# hybrid_esc.net
KiCad netlist of a schematic drawn in EAGLE
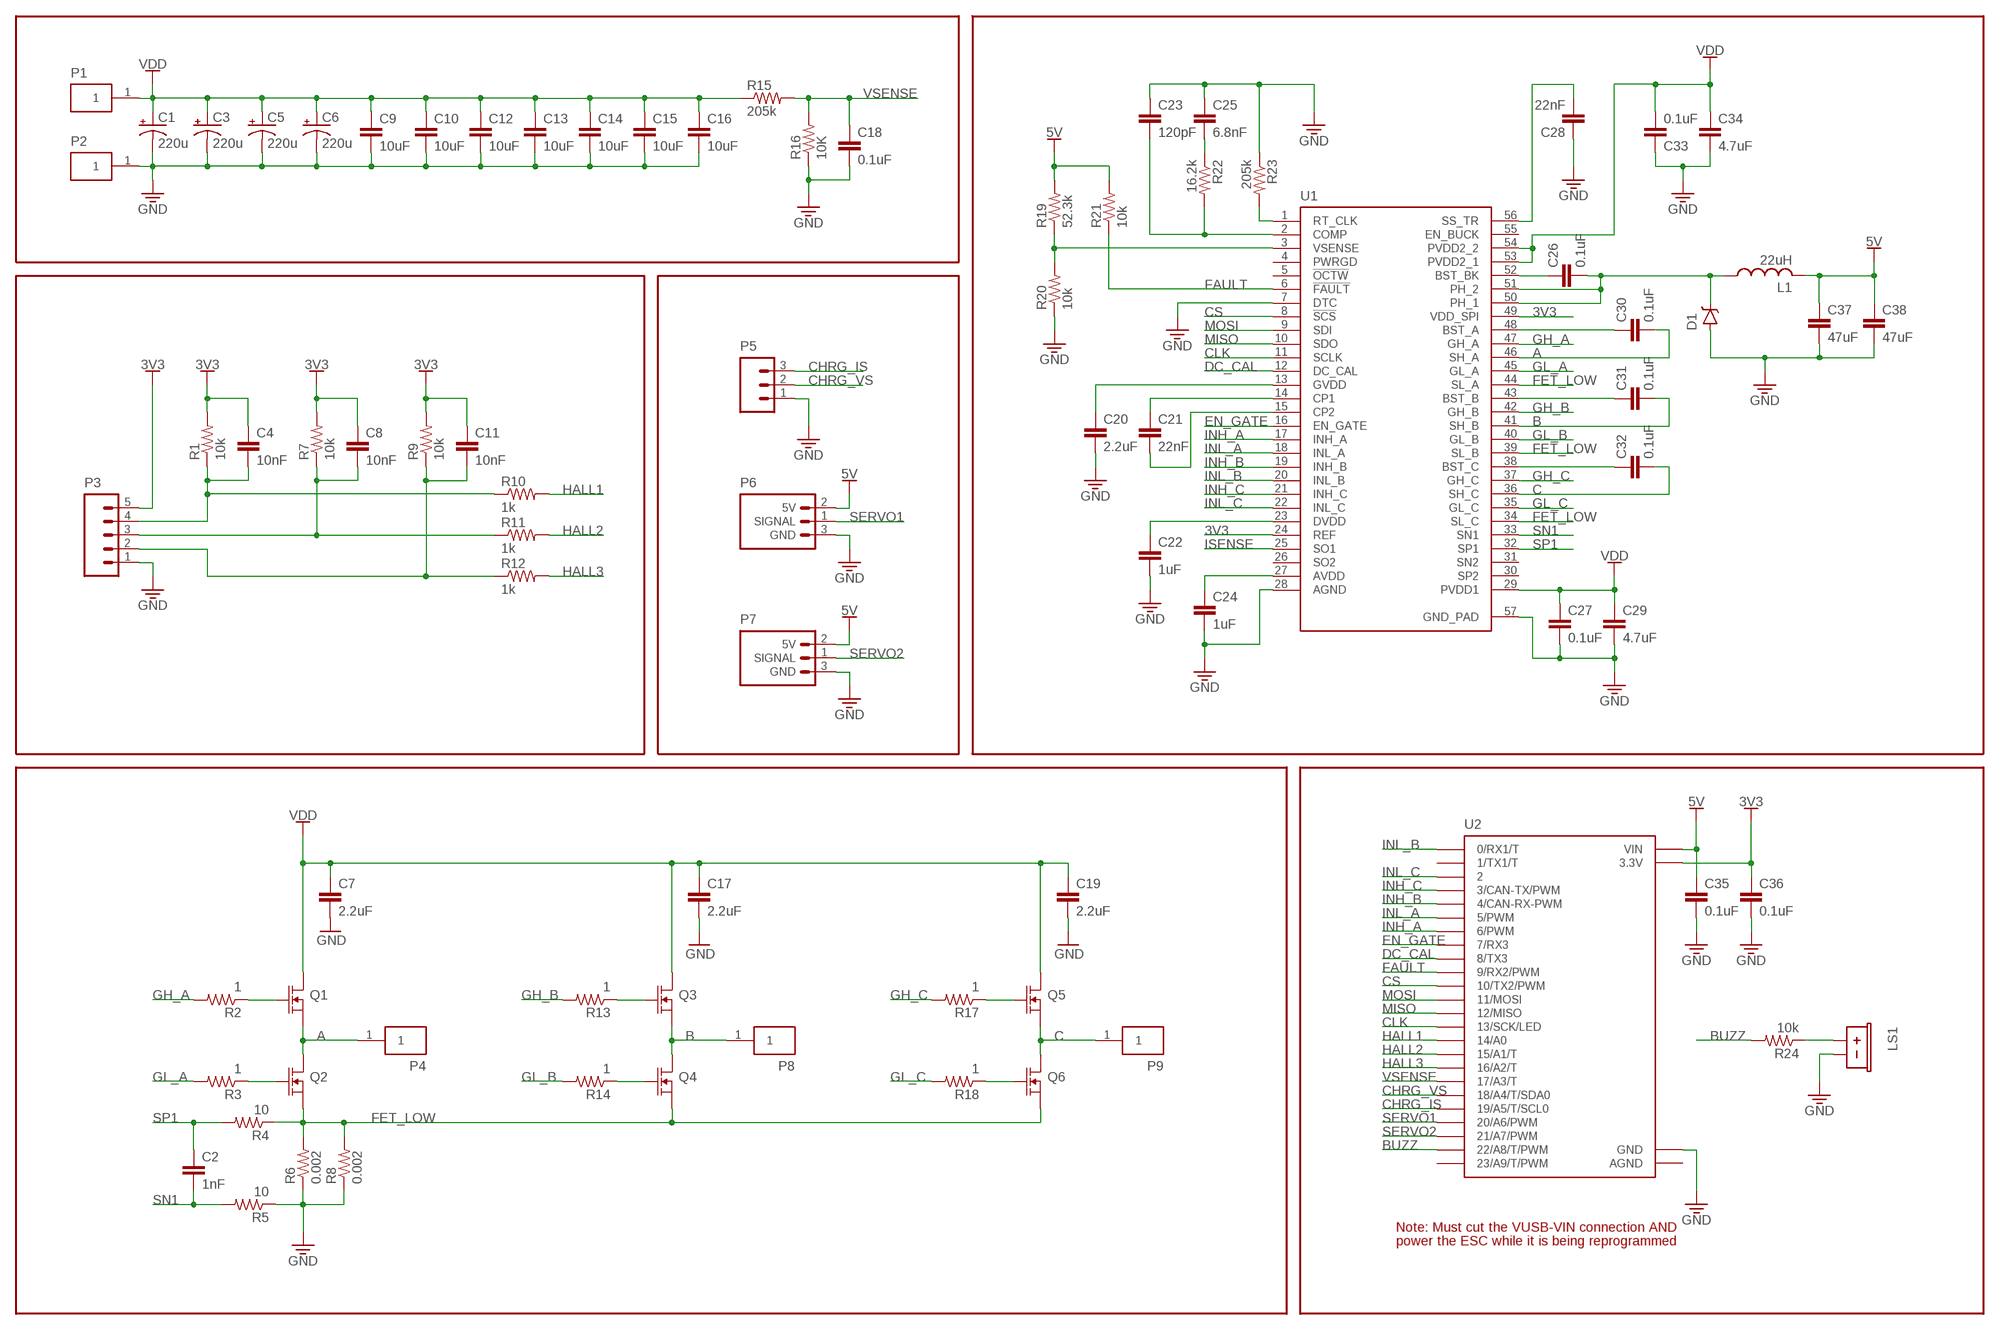
[diagram p0: schematic, sheet 1]

(export (version "E")
  (design (tool "Eeschema 10.0.6"))
  (components
    (comp (ref "C1")
      (value "220u")
      (footprint "eagle-import:CPOL_10_5")
      (libsource (lib "eagle-import") (part "CPOL_10_5"))
    )
    (comp (ref "C2")
      (value "1nF")
      (footprint "eagle-import:C0603")
      (libsource (lib "eagle-import") (part "C0603"))
    )
    (comp (ref "C3")
      (value "220u")
      (footprint "eagle-import:CPOL_10_5")
      (libsource (lib "eagle-import") (part "CPOL_10_5"))
    )
    (comp (ref "C4")
      (value "10nF")
      (footprint "eagle-import:C0603")
      (libsource (lib "eagle-import") (part "C0603"))
    )
    (comp (ref "C5")
      (value "220u")
      (footprint "eagle-import:CPOL_10_5")
      (libsource (lib "eagle-import") (part "CPOL_10_5"))
    )
    (comp (ref "C6")
      (value "220u")
      (footprint "eagle-import:CPOL_10_5")
      (libsource (lib "eagle-import") (part "CPOL_10_5"))
    )
    (comp (ref "C7")
      (value "2.2uF")
      (footprint "eagle-import:C1206")
      (libsource (lib "eagle-import") (part "C1206"))
    )
    (comp (ref "C8")
      (value "10nF")
      (footprint "eagle-import:C0603")
      (libsource (lib "eagle-import") (part "C0603"))
    )
    (comp (ref "C9")
      (value "10uF")
      (footprint "eagle-import:C1206")
      (libsource (lib "eagle-import") (part "C1206"))
    )
    (comp (ref "C10")
      (value "10uF")
      (footprint "eagle-import:C1206")
      (libsource (lib "eagle-import") (part "C1206"))
    )
    (comp (ref "C11")
      (value "10nF")
      (footprint "eagle-import:C0603")
      (libsource (lib "eagle-import") (part "C0603"))
    )
    (comp (ref "C12")
      (value "10uF")
      (footprint "eagle-import:C1206")
      (libsource (lib "eagle-import") (part "C1206"))
    )
    (comp (ref "C13")
      (value "10uF")
      (footprint "eagle-import:C1206")
      (libsource (lib "eagle-import") (part "C1206"))
    )
    (comp (ref "C14")
      (value "10uF")
      (footprint "eagle-import:C1206")
      (libsource (lib "eagle-import") (part "C1206"))
    )
    (comp (ref "C15")
      (value "10uF")
      (footprint "eagle-import:C1206")
      (libsource (lib "eagle-import") (part "C1206"))
    )
    (comp (ref "C16")
      (value "10uF")
      (footprint "eagle-import:C1206")
      (libsource (lib "eagle-import") (part "C1206"))
    )
    (comp (ref "C17")
      (value "2.2uF")
      (footprint "eagle-import:C1206")
      (libsource (lib "eagle-import") (part "C1206"))
    )
    (comp (ref "C18")
      (value "0.1uF")
      (footprint "eagle-import:C0603")
      (libsource (lib "eagle-import") (part "C0603"))
    )
    (comp (ref "C19")
      (value "2.2uF")
      (footprint "eagle-import:C1206")
      (libsource (lib "eagle-import") (part "C1206"))
    )
    (comp (ref "C20")
      (value "2.2uF")
      (footprint "eagle-import:C0603")
      (libsource (lib "eagle-import") (part "C0603"))
    )
    (comp (ref "C21")
      (value "22nF")
      (footprint "eagle-import:C0603")
      (libsource (lib "eagle-import") (part "C0603"))
    )
    (comp (ref "C22")
      (value "1uF")
      (footprint "eagle-import:C0603")
      (libsource (lib "eagle-import") (part "C0603"))
    )
    (comp (ref "C23")
      (value "120pF")
      (footprint "eagle-import:C0603")
      (libsource (lib "eagle-import") (part "C0603"))
    )
    (comp (ref "C24")
      (value "1uF")
      (footprint "eagle-import:C0603")
      (libsource (lib "eagle-import") (part "C0603"))
    )
    (comp (ref "C25")
      (value "6.8nF")
      (footprint "eagle-import:C0603")
      (libsource (lib "eagle-import") (part "C0603"))
    )
    (comp (ref "C26")
      (value "0.1uF")
      (footprint "eagle-import:C0603")
      (libsource (lib "eagle-import") (part "C0603"))
    )
    (comp (ref "C27")
      (value "0.1uF")
      (footprint "eagle-import:C0603")
      (libsource (lib "eagle-import") (part "C0603"))
    )
    (comp (ref "C28")
      (value "22nF")
      (footprint "eagle-import:C0603")
      (libsource (lib "eagle-import") (part "C0603"))
    )
    (comp (ref "C29")
      (value "4.7uF")
      (footprint "eagle-import:C1206")
      (libsource (lib "eagle-import") (part "C1206"))
    )
    (comp (ref "C30")
      (value "0.1uF")
      (footprint "eagle-import:C0603")
      (libsource (lib "eagle-import") (part "C0603"))
    )
    (comp (ref "C31")
      (value "0.1uF")
      (footprint "eagle-import:C0603")
      (libsource (lib "eagle-import") (part "C0603"))
    )
    (comp (ref "C32")
      (value "0.1uF")
      (footprint "eagle-import:C0603")
      (libsource (lib "eagle-import") (part "C0603"))
    )
    (comp (ref "C33")
      (value "0.1uF")
      (footprint "eagle-import:C0603")
      (libsource (lib "eagle-import") (part "C0603"))
    )
    (comp (ref "C34")
      (value "4.7uF")
      (footprint "eagle-import:C1206")
      (libsource (lib "eagle-import") (part "C1206"))
    )
    (comp (ref "C35")
      (value "0.1uF")
      (footprint "eagle-import:C0603")
      (libsource (lib "eagle-import") (part "C0603"))
    )
    (comp (ref "C36")
      (value "0.1uF")
      (footprint "eagle-import:C0603")
      (libsource (lib "eagle-import") (part "C0603"))
    )
    (comp (ref "C37")
      (value "47uF")
      (footprint "eagle-import:C1206")
      (libsource (lib "eagle-import") (part "C1206"))
    )
    (comp (ref "C38")
      (value "47uF")
      (footprint "eagle-import:C1206")
      (libsource (lib "eagle-import") (part "C1206"))
    )
    (comp (ref "D1")
      (value "D_SOD123W")
      (footprint "eagle-import:SOD123W")
      (libsource (lib "eagle-import") (part "D_SOD123W"))
    )
    (comp (ref "L1")
      (value "22uH")
      (footprint "eagle-import:SDR0805")
      (libsource (lib "eagle-import") (part "L_SDR0805"))
    )
    (comp (ref "LS1")
      (value "BUZZER_12MM")
      (footprint "eagle-import:BUZZER_12MM")
      (libsource (lib "eagle-import") (part "BUZZER_12MM"))
    )
    (comp (ref "P1")
      (value "POWER_PAD")
      (footprint "eagle-import:POWER_PAD")
      (libsource (lib "eagle-import") (part "POWER_PAD"))
    )
    (comp (ref "P2")
      (value "POWER_PAD")
      (footprint "eagle-import:POWER_PAD")
      (libsource (lib "eagle-import") (part "POWER_PAD"))
    )
    (comp (ref "P3")
      (value "JST-XH5")
      (footprint "eagle-import:JST-XH5")
      (libsource (lib "eagle-import") (part "JST-XH5"))
    )
    (comp (ref "P4")
      (value "POWER_PAD")
      (footprint "eagle-import:POWER_PAD")
      (libsource (lib "eagle-import") (part "POWER_PAD"))
    )
    (comp (ref "P5")
      (value "CONN_03")
      (footprint "eagle-import:CONN_03")
      (libsource (lib "eagle-import") (part "CONN_03"))
    )
    (comp (ref "P6")
      (value "SERVO")
      (footprint "eagle-import:SERVO")
      (libsource (lib "eagle-import") (part "SERVO"))
    )
    (comp (ref "P7")
      (value "SERVO")
      (footprint "eagle-import:SERVO")
      (libsource (lib "eagle-import") (part "SERVO"))
    )
    (comp (ref "P8")
      (value "POWER_PAD")
      (footprint "eagle-import:POWER_PAD")
      (libsource (lib "eagle-import") (part "POWER_PAD"))
    )
    (comp (ref "P9")
      (value "POWER_PAD")
      (footprint "eagle-import:POWER_PAD")
      (libsource (lib "eagle-import") (part "POWER_PAD"))
    )
    (comp (ref "Q1")
      (value "NFET_D2PAK-7")
      (footprint "eagle-import:D2PAK-7")
      (libsource (lib "eagle-import") (part "NFET_D2PAK-7"))
    )
    (comp (ref "Q2")
      (value "NFET_D2PAK-7")
      (footprint "eagle-import:D2PAK-7")
      (libsource (lib "eagle-import") (part "NFET_D2PAK-7"))
    )
    (comp (ref "Q3")
      (value "NFET_D2PAK-7")
      (footprint "eagle-import:D2PAK-7")
      (libsource (lib "eagle-import") (part "NFET_D2PAK-7"))
    )
    (comp (ref "Q4")
      (value "NFET_D2PAK-7")
      (footprint "eagle-import:D2PAK-7")
      (libsource (lib "eagle-import") (part "NFET_D2PAK-7"))
    )
    (comp (ref "Q5")
      (value "NFET_D2PAK-7")
      (footprint "eagle-import:D2PAK-7")
      (libsource (lib "eagle-import") (part "NFET_D2PAK-7"))
    )
    (comp (ref "Q6")
      (value "NFET_D2PAK-7")
      (footprint "eagle-import:D2PAK-7")
      (libsource (lib "eagle-import") (part "NFET_D2PAK-7"))
    )
    (comp (ref "R1")
      (value "10k")
      (footprint "eagle-import:R0603")
      (libsource (lib "eagle-import") (part "R0603"))
    )
    (comp (ref "R2")
      (value "1")
      (footprint "eagle-import:R0603")
      (libsource (lib "eagle-import") (part "R0603"))
    )
    (comp (ref "R3")
      (value "1")
      (footprint "eagle-import:R0603")
      (libsource (lib "eagle-import") (part "R0603"))
    )
    (comp (ref "R4")
      (value "10")
      (footprint "eagle-import:R0603")
      (libsource (lib "eagle-import") (part "R0603"))
    )
    (comp (ref "R5")
      (value "10")
      (footprint "eagle-import:R0603")
      (libsource (lib "eagle-import") (part "R0603"))
    )
    (comp (ref "R6")
      (value "0.002")
      (footprint "eagle-import:R2512")
      (libsource (lib "eagle-import") (part "R2512"))
    )
    (comp (ref "R7")
      (value "10k")
      (footprint "eagle-import:R0603")
      (libsource (lib "eagle-import") (part "R0603"))
    )
    (comp (ref "R8")
      (value "0.002")
      (footprint "eagle-import:R2512")
      (libsource (lib "eagle-import") (part "R2512"))
    )
    (comp (ref "R9")
      (value "10k")
      (footprint "eagle-import:R0603")
      (libsource (lib "eagle-import") (part "R0603"))
    )
    (comp (ref "R10")
      (value "1k")
      (footprint "eagle-import:R0603")
      (libsource (lib "eagle-import") (part "R0603"))
    )
    (comp (ref "R11")
      (value "1k")
      (footprint "eagle-import:R0603")
      (libsource (lib "eagle-import") (part "R0603"))
    )
    (comp (ref "R12")
      (value "1k")
      (footprint "eagle-import:R0603")
      (libsource (lib "eagle-import") (part "R0603"))
    )
    (comp (ref "R13")
      (value "1")
      (footprint "eagle-import:R0603")
      (libsource (lib "eagle-import") (part "R0603"))
    )
    (comp (ref "R14")
      (value "1")
      (footprint "eagle-import:R0603")
      (libsource (lib "eagle-import") (part "R0603"))
    )
    (comp (ref "R15")
      (value "205k")
      (footprint "eagle-import:R0603")
      (libsource (lib "eagle-import") (part "R0603"))
    )
    (comp (ref "R16")
      (value "10K")
      (footprint "eagle-import:R0603")
      (libsource (lib "eagle-import") (part "R0603"))
    )
    (comp (ref "R17")
      (value "1")
      (footprint "eagle-import:R0603")
      (libsource (lib "eagle-import") (part "R0603"))
    )
    (comp (ref "R18")
      (value "1")
      (footprint "eagle-import:R0603")
      (libsource (lib "eagle-import") (part "R0603"))
    )
    (comp (ref "R19")
      (value "52.3k")
      (footprint "eagle-import:R0603")
      (libsource (lib "eagle-import") (part "R0603"))
    )
    (comp (ref "R20")
      (value "10k")
      (footprint "eagle-import:R0603")
      (libsource (lib "eagle-import") (part "R0603"))
    )
    (comp (ref "R21")
      (value "10k")
      (footprint "eagle-import:R0603")
      (libsource (lib "eagle-import") (part "R0603"))
    )
    (comp (ref "R22")
      (value "16.2k")
      (footprint "eagle-import:R0603")
      (libsource (lib "eagle-import") (part "R0603"))
    )
    (comp (ref "R23")
      (value "205k")
      (footprint "eagle-import:R0603")
      (libsource (lib "eagle-import") (part "R0603"))
    )
    (comp (ref "R24")
      (value "10k")
      (footprint "eagle-import:R0603")
      (libsource (lib "eagle-import") (part "R0603"))
    )
    (comp (ref "U1")
      (value "DRV8301")
      (footprint "eagle-import:TSSOP56P")
      (libsource (lib "eagle-import") (part "DRV8301"))
    )
    (comp (ref "U2")
      (value "TEENSY_3.1")
      (footprint "eagle-import:TEENSY_3.1")
      (libsource (lib "eagle-import") (part "TEENSY_3.1"))
    )
  )
  (nets
    (net (code "1") (name "/A") (class "Default")
      (node (ref "C30") (pin "2") (pinfunction "2_2") (pintype "passive"))
      (node (ref "P4") (pin "1") (pinfunction "1_1") (pintype "bidirectional"))
      (node (ref "Q1") (pin "S") (pinfunction "S_S") (pintype "bidirectional"))
      (node (ref "Q1") (pin "S1") (pinfunction "S_S1") (pintype "bidirectional"))
      (node (ref "Q1") (pin "S2") (pinfunction "S_S2") (pintype "bidirectional"))
      (node (ref "Q1") (pin "S3") (pinfunction "S_S3") (pintype "bidirectional"))
      (node (ref "Q1") (pin "S4") (pinfunction "S_S4") (pintype "bidirectional"))
      (node (ref "Q2") (pin "D") (pinfunction "D_D") (pintype "bidirectional"))
      (node (ref "U1") (pin "46") (pinfunction "SH_A_46") (pintype "bidirectional"))
    )
    (net (code "2") (name "/AGND") (class "Default")
      (node (ref "U2") (pin "AGND") (pinfunction "AGND_AGND") (pintype "power_in"))
    )
    (net (code "3") (name "/B") (class "Default")
      (node (ref "C31") (pin "2") (pinfunction "2_2") (pintype "passive"))
      (node (ref "P8") (pin "1") (pinfunction "1_1") (pintype "bidirectional"))
      (node (ref "Q3") (pin "S") (pinfunction "S_S") (pintype "bidirectional"))
      (node (ref "Q3") (pin "S1") (pinfunction "S_S1") (pintype "bidirectional"))
      (node (ref "Q3") (pin "S2") (pinfunction "S_S2") (pintype "bidirectional"))
      (node (ref "Q3") (pin "S3") (pinfunction "S_S3") (pintype "bidirectional"))
      (node (ref "Q3") (pin "S4") (pinfunction "S_S4") (pintype "bidirectional"))
      (node (ref "Q4") (pin "D") (pinfunction "D_D") (pintype "bidirectional"))
      (node (ref "U1") (pin "41") (pinfunction "SH_B_41") (pintype "bidirectional"))
    )
    (net (code "4") (name "/BUZZ") (class "Default")
      (node (ref "R24") (pin "2") (pinfunction "2_2") (pintype "passive"))
      (node (ref "U2") (pin "22/A8") (pinfunction "22/A8/T/PWM_22/A8") (pintype "bidirectional"))
    )
    (net (code "5") (name "/C") (class "Default")
      (node (ref "C32") (pin "2") (pinfunction "2_2") (pintype "passive"))
      (node (ref "P9") (pin "1") (pinfunction "1_1") (pintype "bidirectional"))
      (node (ref "Q5") (pin "S") (pinfunction "S_S") (pintype "bidirectional"))
      (node (ref "Q5") (pin "S1") (pinfunction "S_S1") (pintype "bidirectional"))
      (node (ref "Q5") (pin "S2") (pinfunction "S_S2") (pintype "bidirectional"))
      (node (ref "Q5") (pin "S3") (pinfunction "S_S3") (pintype "bidirectional"))
      (node (ref "Q5") (pin "S4") (pinfunction "S_S4") (pintype "bidirectional"))
      (node (ref "Q6") (pin "D") (pinfunction "D_D") (pintype "bidirectional"))
      (node (ref "U1") (pin "36") (pinfunction "SH_C_36") (pintype "bidirectional"))
    )
    (net (code "6") (name "/CHRG_IS") (class "Default")
      (node (ref "P5") (pin "3") (pinfunction "3_3") (pintype "bidirectional"))
      (node (ref "U2") (pin "19/A5") (pinfunction "19/A5/T/SCL0_19/A5") (pintype "bidirectional"))
    )
    (net (code "7") (name "/CHRG_VS") (class "Default")
      (node (ref "P5") (pin "2") (pinfunction "2_2") (pintype "bidirectional"))
      (node (ref "U2") (pin "18/A4") (pinfunction "18/A4/T/SDA0_18/A4") (pintype "bidirectional"))
    )
    (net (code "8") (name "/CLK") (class "Default")
      (node (ref "U1") (pin "11") (pinfunction "SCLK_11") (pintype "bidirectional"))
      (node (ref "U2") (pin "13") (pinfunction "13/SCK/LED_13") (pintype "bidirectional"))
    )
    (net (code "9") (name "/CS") (class "Default")
      (node (ref "U1") (pin "8") (pinfunction "~{SCS}_8") (pintype "bidirectional"))
      (node (ref "U2") (pin "10") (pinfunction "10/TX2/PWM_10") (pintype "bidirectional"))
    )
    (net (code "10") (name "/DC_CAL") (class "Default")
      (node (ref "U1") (pin "12") (pinfunction "DC_CAL_12") (pintype "bidirectional"))
      (node (ref "U2") (pin "8") (pinfunction "8/TX3_8") (pintype "bidirectional"))
    )
    (net (code "11") (name "/EN_GATE") (class "Default")
      (node (ref "U1") (pin "16") (pinfunction "EN_GATE_16") (pintype "bidirectional"))
      (node (ref "U2") (pin "7") (pinfunction "7/RX3_7") (pintype "bidirectional"))
    )
    (net (code "12") (name "/FAULT") (class "Default")
      (node (ref "R21") (pin "1") (pinfunction "1_1") (pintype "passive"))
      (node (ref "U1") (pin "6") (pinfunction "~{FAULT}_6") (pintype "bidirectional"))
      (node (ref "U2") (pin "9") (pinfunction "9/RX2/PWM_9") (pintype "bidirectional"))
    )
    (net (code "13") (name "/FET_LOW") (class "Default")
      (node (ref "Q2") (pin "S") (pinfunction "S_S") (pintype "bidirectional"))
      (node (ref "Q2") (pin "S1") (pinfunction "S_S1") (pintype "bidirectional"))
      (node (ref "Q2") (pin "S2") (pinfunction "S_S2") (pintype "bidirectional"))
      (node (ref "Q2") (pin "S3") (pinfunction "S_S3") (pintype "bidirectional"))
      (node (ref "Q2") (pin "S4") (pinfunction "S_S4") (pintype "bidirectional"))
      (node (ref "Q4") (pin "S") (pinfunction "S_S") (pintype "bidirectional"))
      (node (ref "Q4") (pin "S1") (pinfunction "S_S1") (pintype "bidirectional"))
      (node (ref "Q4") (pin "S2") (pinfunction "S_S2") (pintype "bidirectional"))
      (node (ref "Q4") (pin "S3") (pinfunction "S_S3") (pintype "bidirectional"))
      (node (ref "Q4") (pin "S4") (pinfunction "S_S4") (pintype "bidirectional"))
      (node (ref "Q6") (pin "S") (pinfunction "S_S") (pintype "bidirectional"))
      (node (ref "Q6") (pin "S1") (pinfunction "S_S1") (pintype "bidirectional"))
      (node (ref "Q6") (pin "S2") (pinfunction "S_S2") (pintype "bidirectional"))
      (node (ref "Q6") (pin "S3") (pinfunction "S_S3") (pintype "bidirectional"))
      (node (ref "Q6") (pin "S4") (pinfunction "S_S4") (pintype "bidirectional"))
      (node (ref "R4") (pin "1") (pinfunction "1_1") (pintype "passive"))
      (node (ref "R6") (pin "2") (pinfunction "2_2") (pintype "passive"))
      (node (ref "R8") (pin "2") (pinfunction "2_2") (pintype "passive"))
      (node (ref "U1") (pin "34") (pinfunction "SL_C_34") (pintype "bidirectional"))
      (node (ref "U1") (pin "39") (pinfunction "SL_B_39") (pintype "bidirectional"))
      (node (ref "U1") (pin "44") (pinfunction "SL_A_44") (pintype "bidirectional"))
    )
    (net (code "14") (name "/GH_A") (class "Default")
      (node (ref "R2") (pin "2") (pinfunction "2_2") (pintype "passive"))
      (node (ref "U1") (pin "47") (pinfunction "GH_A_47") (pintype "bidirectional"))
    )
    (net (code "15") (name "/GH_B") (class "Default")
      (node (ref "R13") (pin "2") (pinfunction "2_2") (pintype "passive"))
      (node (ref "U1") (pin "42") (pinfunction "GH_B_42") (pintype "bidirectional"))
    )
    (net (code "16") (name "/GH_C") (class "Default")
      (node (ref "R17") (pin "2") (pinfunction "2_2") (pintype "passive"))
      (node (ref "U1") (pin "37") (pinfunction "GH_C_37") (pintype "bidirectional"))
    )
    (net (code "17") (name "/GL_A") (class "Default")
      (node (ref "R3") (pin "2") (pinfunction "2_2") (pintype "passive"))
      (node (ref "U1") (pin "45") (pinfunction "GL_A_45") (pintype "bidirectional"))
    )
    (net (code "18") (name "/GL_B") (class "Default")
      (node (ref "R14") (pin "2") (pinfunction "2_2") (pintype "passive"))
      (node (ref "U1") (pin "40") (pinfunction "GL_B_40") (pintype "bidirectional"))
    )
    (net (code "19") (name "/GL_C") (class "Default")
      (node (ref "R18") (pin "2") (pinfunction "2_2") (pintype "passive"))
      (node (ref "U1") (pin "35") (pinfunction "GL_C_35") (pintype "bidirectional"))
    )
    (net (code "20") (name "/HALL1") (class "Default")
      (node (ref "R10") (pin "2") (pinfunction "2_2") (pintype "passive"))
      (node (ref "U2") (pin "14/A0") (pinfunction "14/A0_14/A0") (pintype "bidirectional"))
    )
    (net (code "21") (name "/HALL2") (class "Default")
      (node (ref "R11") (pin "2") (pinfunction "2_2") (pintype "passive"))
      (node (ref "U2") (pin "15/A1") (pinfunction "15/A1/T_15/A1") (pintype "bidirectional"))
    )
    (net (code "22") (name "/HALL3") (class "Default")
      (node (ref "R12") (pin "2") (pinfunction "2_2") (pintype "passive"))
      (node (ref "U2") (pin "16/A2") (pinfunction "16/A2/T_16/A2") (pintype "bidirectional"))
    )
    (net (code "23") (name "/INH_A") (class "Default")
      (node (ref "U1") (pin "17") (pinfunction "INH_A_17") (pintype "bidirectional"))
      (node (ref "U2") (pin "6") (pinfunction "6/PWM_6") (pintype "bidirectional"))
    )
    (net (code "24") (name "/INH_B") (class "Default")
      (node (ref "U1") (pin "19") (pinfunction "INH_B_19") (pintype "bidirectional"))
      (node (ref "U2") (pin "4") (pinfunction "4/CAN-RX-PWM_4") (pintype "bidirectional"))
    )
    (net (code "25") (name "/INH_C") (class "Default")
      (node (ref "U1") (pin "21") (pinfunction "INH_C_21") (pintype "bidirectional"))
      (node (ref "U2") (pin "3") (pinfunction "3/CAN-TX/PWM_3") (pintype "bidirectional"))
    )
    (net (code "26") (name "/INL_A") (class "Default")
      (node (ref "U1") (pin "18") (pinfunction "INL_A_18") (pintype "bidirectional"))
      (node (ref "U2") (pin "5") (pinfunction "5/PWM_5") (pintype "bidirectional"))
    )
    (net (code "27") (name "/INL_B") (class "Default")
      (node (ref "U1") (pin "20") (pinfunction "INL_B_20") (pintype "bidirectional"))
      (node (ref "U2") (pin "0") (pinfunction "0/RX1/T_0") (pintype "bidirectional"))
    )
    (net (code "28") (name "/INL_C") (class "Default")
      (node (ref "U1") (pin "22") (pinfunction "INL_C_22") (pintype "bidirectional"))
      (node (ref "U2") (pin "2") (pinfunction "2_2") (pintype "bidirectional"))
    )
    (net (code "29") (name "/ISENSE") (class "Default")
      (node (ref "U1") (pin "25") (pinfunction "SO1_25") (pintype "bidirectional"))
    )
    (net (code "30") (name "/MISO") (class "Default")
      (node (ref "U1") (pin "10") (pinfunction "SDO_10") (pintype "bidirectional"))
      (node (ref "U2") (pin "12") (pinfunction "12/MISO_12") (pintype "bidirectional"))
    )
    (net (code "31") (name "/MOSI") (class "Default")
      (node (ref "U1") (pin "9") (pinfunction "SDI_9") (pintype "bidirectional"))
      (node (ref "U2") (pin "11") (pinfunction "11/MOSI_11") (pintype "bidirectional"))
    )
    (net (code "32") (name "/SERVO1") (class "Default")
      (node (ref "P6") (pin "1") (pinfunction "SIGNAL_1") (pintype "bidirectional"))
      (node (ref "U2") (pin "20/A6") (pinfunction "20/A6/PWM_20/A6") (pintype "bidirectional"))
    )
    (net (code "33") (name "/SERVO2") (class "Default")
      (node (ref "P7") (pin "1") (pinfunction "SIGNAL_1") (pintype "bidirectional"))
      (node (ref "U2") (pin "21/A7") (pinfunction "21/A7/PWM_21/A7") (pintype "bidirectional"))
    )
    (net (code "34") (name "/SN1") (class "Default")
      (node (ref "C2") (pin "2") (pinfunction "2_2") (pintype "passive"))
      (node (ref "R5") (pin "2") (pinfunction "2_2") (pintype "passive"))
      (node (ref "U1") (pin "33") (pinfunction "SN1_33") (pintype "bidirectional"))
    )
    (net (code "35") (name "/SP1") (class "Default")
      (node (ref "C2") (pin "1") (pinfunction "1_1") (pintype "passive"))
      (node (ref "R4") (pin "2") (pinfunction "2_2") (pintype "passive"))
      (node (ref "U1") (pin "32") (pinfunction "SP1_32") (pintype "bidirectional"))
    )
    (net (code "36") (name "/VSENSE") (class "Default")
      (node (ref "C18") (pin "1") (pinfunction "1_1") (pintype "passive"))
      (node (ref "R15") (pin "2") (pinfunction "2_2") (pintype "passive"))
      (node (ref "R16") (pin "2") (pinfunction "2_2") (pintype "passive"))
      (node (ref "U2") (pin "17/A3") (pinfunction "17/A3/T_17/A3") (pintype "bidirectional"))
    )
    (net (code "37") (name "3V3") (class "Default")
      (node (ref "C11") (pin "1") (pinfunction "1_1") (pintype "passive"))
      (node (ref "C36") (pin "1") (pinfunction "1_1") (pintype "passive"))
      (node (ref "C4") (pin "1") (pinfunction "1_1") (pintype "passive"))
      (node (ref "C8") (pin "1") (pinfunction "1_1") (pintype "passive"))
      (node (ref "P3") (pin "5") (pinfunction "5_5") (pintype "bidirectional"))
      (node (ref "R1") (pin "2") (pinfunction "2_2") (pintype "passive"))
      (node (ref "R7") (pin "2") (pinfunction "2_2") (pintype "passive"))
      (node (ref "R9") (pin "2") (pinfunction "2_2") (pintype "passive"))
      (node (ref "U1") (pin "24") (pinfunction "REF_24") (pintype "bidirectional"))
      (node (ref "U1") (pin "49") (pinfunction "VDD_SPI_49") (pintype "bidirectional"))
      (node (ref "U2") (pin "3.3V") (pinfunction "3.3V_3.3V") (pintype "power_in"))
    )
    (net (code "38") (name "5V") (class "Default")
      (node (ref "C35") (pin "1") (pinfunction "1_1") (pintype "passive"))
      (node (ref "C37") (pin "1") (pinfunction "1_1") (pintype "passive"))
      (node (ref "C38") (pin "1") (pinfunction "1_1") (pintype "passive"))
      (node (ref "L1") (pin "2") (pinfunction "2_2") (pintype "passive"))
      (node (ref "P6") (pin "2") (pinfunction "5V_2") (pintype "bidirectional"))
      (node (ref "P7") (pin "2") (pinfunction "5V_2") (pintype "bidirectional"))
      (node (ref "R19") (pin "2") (pinfunction "2_2") (pintype "passive"))
      (node (ref "R21") (pin "2") (pinfunction "2_2") (pintype "passive"))
      (node (ref "U2") (pin "VIN") (pinfunction "VIN_VIN") (pintype "power_in"))
    )
    (net (code "39") (name "GND") (class "Default")
      (node (ref "C1") (pin "-") (pinfunction "-_-") (pintype "passive"))
      (node (ref "C10") (pin "2") (pinfunction "2_2") (pintype "passive"))
      (node (ref "C12") (pin "2") (pinfunction "2_2") (pintype "passive"))
      (node (ref "C13") (pin "2") (pinfunction "2_2") (pintype "passive"))
      (node (ref "C14") (pin "2") (pinfunction "2_2") (pintype "passive"))
      (node (ref "C15") (pin "2") (pinfunction "2_2") (pintype "passive"))
      (node (ref "C16") (pin "2") (pinfunction "2_2") (pintype "passive"))
      (node (ref "C17") (pin "2") (pinfunction "2_2") (pintype "passive"))
      (node (ref "C18") (pin "2") (pinfunction "2_2") (pintype "passive"))
      (node (ref "C19") (pin "2") (pinfunction "2_2") (pintype "passive"))
      (node (ref "C20") (pin "2") (pinfunction "2_2") (pintype "passive"))
      (node (ref "C22") (pin "2") (pinfunction "2_2") (pintype "passive"))
      (node (ref "C23") (pin "1") (pinfunction "1_1") (pintype "passive"))
      (node (ref "C24") (pin "2") (pinfunction "2_2") (pintype "passive"))
      (node (ref "C25") (pin "1") (pinfunction "1_1") (pintype "passive"))
      (node (ref "C27") (pin "2") (pinfunction "2_2") (pintype "passive"))
      (node (ref "C28") (pin "1") (pinfunction "1_1") (pintype "passive"))
      (node (ref "C29") (pin "2") (pinfunction "2_2") (pintype "passive"))
      (node (ref "C3") (pin "-") (pinfunction "-_-") (pintype "passive"))
      (node (ref "C33") (pin "1") (pinfunction "1_1") (pintype "passive"))
      (node (ref "C34") (pin "2") (pinfunction "2_2") (pintype "passive"))
      (node (ref "C35") (pin "2") (pinfunction "2_2") (pintype "passive"))
      (node (ref "C36") (pin "2") (pinfunction "2_2") (pintype "passive"))
      (node (ref "C37") (pin "2") (pinfunction "2_2") (pintype "passive"))
      (node (ref "C38") (pin "2") (pinfunction "2_2") (pintype "passive"))
      (node (ref "C5") (pin "-") (pinfunction "-_-") (pintype "passive"))
      (node (ref "C6") (pin "-") (pinfunction "-_-") (pintype "passive"))
      (node (ref "C7") (pin "2") (pinfunction "2_2") (pintype "passive"))
      (node (ref "C9") (pin "2") (pinfunction "2_2") (pintype "passive"))
      (node (ref "D1") (pin "A") (pinfunction "A_A") (pintype "passive"))
      (node (ref "LS1") (pin "-") (pinfunction "-_-") (pintype "passive"))
      (node (ref "P2") (pin "1") (pinfunction "1_1") (pintype "bidirectional"))
      (node (ref "P3") (pin "1") (pinfunction "1_1") (pintype "bidirectional"))
      (node (ref "P5") (pin "1") (pinfunction "1_1") (pintype "bidirectional"))
      (node (ref "P6") (pin "3") (pinfunction "GND_3") (pintype "bidirectional"))
      (node (ref "P7") (pin "3") (pinfunction "GND_3") (pintype "bidirectional"))
      (node (ref "R16") (pin "1") (pinfunction "1_1") (pintype "passive"))
      (node (ref "R20") (pin "1") (pinfunction "1_1") (pintype "passive"))
      (node (ref "R23") (pin "1") (pinfunction "1_1") (pintype "passive"))
      (node (ref "R5") (pin "1") (pinfunction "1_1") (pintype "passive"))
      (node (ref "R6") (pin "1") (pinfunction "1_1") (pintype "passive"))
      (node (ref "R8") (pin "1") (pinfunction "1_1") (pintype "passive"))
      (node (ref "U1") (pin "28") (pinfunction "AGND_28") (pintype "bidirectional"))
      (node (ref "U1") (pin "57") (pinfunction "GND_PAD_57") (pintype "bidirectional"))
      (node (ref "U1") (pin "7") (pinfunction "DTC_7") (pintype "bidirectional"))
      (node (ref "U2") (pin "GND") (pinfunction "GND_GND") (pintype "power_in"))
    )
    (net (code "40") (name "Net-(C4-Pad2)") (class "Default")
      (node (ref "C4") (pin "2") (pinfunction "2_2") (pintype "passive"))
      (node (ref "P3") (pin "4") (pinfunction "4_4") (pintype "bidirectional"))
      (node (ref "R1") (pin "1") (pinfunction "1_1") (pintype "passive"))
      (node (ref "R10") (pin "1") (pinfunction "1_1") (pintype "passive"))
    )
    (net (code "41") (name "Net-(C8-Pad2)") (class "Default")
      (node (ref "C8") (pin "2") (pinfunction "2_2") (pintype "passive"))
      (node (ref "P3") (pin "3") (pinfunction "3_3") (pintype "bidirectional"))
      (node (ref "R11") (pin "1") (pinfunction "1_1") (pintype "passive"))
      (node (ref "R7") (pin "1") (pinfunction "1_1") (pintype "passive"))
    )
    (net (code "42") (name "Net-(C11-Pad2)") (class "Default")
      (node (ref "C11") (pin "2") (pinfunction "2_2") (pintype "passive"))
      (node (ref "P3") (pin "2") (pinfunction "2_2") (pintype "bidirectional"))
      (node (ref "R12") (pin "1") (pinfunction "1_1") (pintype "passive"))
      (node (ref "R9") (pin "1") (pinfunction "1_1") (pintype "passive"))
    )
    (net (code "43") (name "Net-(C25-Pad2)") (class "Default")
      (node (ref "C25") (pin "2") (pinfunction "2_2") (pintype "passive"))
      (node (ref "R22") (pin "1") (pinfunction "1_1") (pintype "passive"))
    )
    (net (code "44") (name "Net-(LS1-Pad+)") (class "Default")
      (node (ref "LS1") (pin "+") (pinfunction "+_+") (pintype "passive"))
      (node (ref "R24") (pin "1") (pinfunction "1_1") (pintype "passive"))
    )
    (net (code "45") (name "Net-(Q1-PadG)") (class "Default")
      (node (ref "Q1") (pin "G") (pinfunction "G_G") (pintype "bidirectional"))
      (node (ref "R2") (pin "1") (pinfunction "1_1") (pintype "passive"))
    )
    (net (code "46") (name "Net-(Q2-PadG)") (class "Default")
      (node (ref "Q2") (pin "G") (pinfunction "G_G") (pintype "bidirectional"))
      (node (ref "R3") (pin "1") (pinfunction "1_1") (pintype "passive"))
    )
    (net (code "47") (name "Net-(Q3-PadG)") (class "Default")
      (node (ref "Q3") (pin "G") (pinfunction "G_G") (pintype "bidirectional"))
      (node (ref "R13") (pin "1") (pinfunction "1_1") (pintype "passive"))
    )
    (net (code "48") (name "Net-(Q4-PadG)") (class "Default")
      (node (ref "Q4") (pin "G") (pinfunction "G_G") (pintype "bidirectional"))
      (node (ref "R14") (pin "1") (pinfunction "1_1") (pintype "passive"))
    )
    (net (code "49") (name "Net-(Q5-PadG)") (class "Default")
      (node (ref "Q5") (pin "G") (pinfunction "G_G") (pintype "bidirectional"))
      (node (ref "R17") (pin "1") (pinfunction "1_1") (pintype "passive"))
    )
    (net (code "50") (name "Net-(Q6-PadG)") (class "Default")
      (node (ref "Q6") (pin "G") (pinfunction "G_G") (pintype "bidirectional"))
      (node (ref "R18") (pin "1") (pinfunction "1_1") (pintype "passive"))
    )
    (net (code "51") (name "Net-(U1-AVDD)") (class "Default")
      (node (ref "C24") (pin "1") (pinfunction "1_1") (pintype "passive"))
      (node (ref "U1") (pin "27") (pinfunction "AVDD_27") (pintype "bidirectional"))
    )
    (net (code "52") (name "Net-(U1-BST_A)") (class "Default")
      (node (ref "C30") (pin "1") (pinfunction "1_1") (pintype "passive"))
      (node (ref "U1") (pin "48") (pinfunction "BST_A_48") (pintype "bidirectional"))
    )
    (net (code "53") (name "Net-(U1-BST_B)") (class "Default")
      (node (ref "C31") (pin "1") (pinfunction "1_1") (pintype "passive"))
      (node (ref "U1") (pin "43") (pinfunction "BST_B_43") (pintype "bidirectional"))
    )
    (net (code "54") (name "Net-(U1-BST_BK)") (class "Default")
      (node (ref "C26") (pin "1") (pinfunction "1_1") (pintype "passive"))
      (node (ref "U1") (pin "52") (pinfunction "BST_BK_52") (pintype "bidirectional"))
    )
    (net (code "55") (name "Net-(U1-BST_C)") (class "Default")
      (node (ref "C32") (pin "1") (pinfunction "1_1") (pintype "passive"))
      (node (ref "U1") (pin "38") (pinfunction "BST_C_38") (pintype "bidirectional"))
    )
    (net (code "56") (name "Net-(U1-COMP)") (class "Default")
      (node (ref "C23") (pin "2") (pinfunction "2_2") (pintype "passive"))
      (node (ref "R22") (pin "2") (pinfunction "2_2") (pintype "passive"))
      (node (ref "U1") (pin "2") (pinfunction "COMP_2") (pintype "bidirectional"))
    )
    (net (code "57") (name "Net-(U1-CP1)") (class "Default")
      (node (ref "C21") (pin "1") (pinfunction "1_1") (pintype "passive"))
      (node (ref "U1") (pin "14") (pinfunction "CP1_14") (pintype "bidirectional"))
    )
    (net (code "58") (name "Net-(U1-CP2)") (class "Default")
      (node (ref "C21") (pin "2") (pinfunction "2_2") (pintype "passive"))
      (node (ref "U1") (pin "15") (pinfunction "CP2_15") (pintype "bidirectional"))
    )
    (net (code "59") (name "Net-(U1-DVDD)") (class "Default")
      (node (ref "C22") (pin "1") (pinfunction "1_1") (pintype "passive"))
      (node (ref "U1") (pin "23") (pinfunction "DVDD_23") (pintype "bidirectional"))
    )
    (net (code "60") (name "Net-(U1-GVDD)") (class "Default")
      (node (ref "C20") (pin "1") (pinfunction "1_1") (pintype "passive"))
      (node (ref "U1") (pin "13") (pinfunction "GVDD_13") (pintype "bidirectional"))
    )
    (net (code "61") (name "Net-(U1-PH_1)") (class "Default")
      (node (ref "C26") (pin "2") (pinfunction "2_2") (pintype "passive"))
      (node (ref "D1") (pin "C") (pinfunction "C_C") (pintype "passive"))
      (node (ref "L1") (pin "1") (pinfunction "1_1") (pintype "passive"))
      (node (ref "U1") (pin "50") (pinfunction "PH_1_50") (pintype "bidirectional"))
      (node (ref "U1") (pin "51") (pinfunction "PH_2_51") (pintype "bidirectional"))
    )
    (net (code "62") (name "Net-(U1-RT_CLK)") (class "Default")
      (node (ref "R23") (pin "2") (pinfunction "2_2") (pintype "passive"))
      (node (ref "U1") (pin "1") (pinfunction "RT_CLK_1") (pintype "bidirectional"))
    )
    (net (code "63") (name "Net-(U1-SS_TR)") (class "Default")
      (node (ref "C28") (pin "2") (pinfunction "2_2") (pintype "passive"))
      (node (ref "U1") (pin "56") (pinfunction "SS_TR_56") (pintype "bidirectional"))
    )
    (net (code "64") (name "Net-(U1-VSENSE)") (class "Default")
      (node (ref "R19") (pin "1") (pinfunction "1_1") (pintype "passive"))
      (node (ref "R20") (pin "2") (pinfunction "2_2") (pintype "passive"))
      (node (ref "U1") (pin "3") (pinfunction "VSENSE_3") (pintype "bidirectional"))
    )
    (net (code "65") (name "VDD") (class "Default")
      (node (ref "C1") (pin "+") (pinfunction "+_+") (pintype "passive"))
      (node (ref "C10") (pin "1") (pinfunction "1_1") (pintype "passive"))
      (node (ref "C12") (pin "1") (pinfunction "1_1") (pintype "passive"))
      (node (ref "C13") (pin "1") (pinfunction "1_1") (pintype "passive"))
      (node (ref "C14") (pin "1") (pinfunction "1_1") (pintype "passive"))
      (node (ref "C15") (pin "1") (pinfunction "1_1") (pintype "passive"))
      (node (ref "C16") (pin "1") (pinfunction "1_1") (pintype "passive"))
      (node (ref "C17") (pin "1") (pinfunction "1_1") (pintype "passive"))
      (node (ref "C19") (pin "1") (pinfunction "1_1") (pintype "passive"))
      (node (ref "C27") (pin "1") (pinfunction "1_1") (pintype "passive"))
      (node (ref "C29") (pin "1") (pinfunction "1_1") (pintype "passive"))
      (node (ref "C3") (pin "+") (pinfunction "+_+") (pintype "passive"))
      (node (ref "C33") (pin "2") (pinfunction "2_2") (pintype "passive"))
      (node (ref "C34") (pin "1") (pinfunction "1_1") (pintype "passive"))
      (node (ref "C5") (pin "+") (pinfunction "+_+") (pintype "passive"))
      (node (ref "C6") (pin "+") (pinfunction "+_+") (pintype "passive"))
      (node (ref "C7") (pin "1") (pinfunction "1_1") (pintype "passive"))
      (node (ref "C9") (pin "1") (pinfunction "1_1") (pintype "passive"))
      (node (ref "P1") (pin "1") (pinfunction "1_1") (pintype "bidirectional"))
      (node (ref "Q1") (pin "D") (pinfunction "D_D") (pintype "bidirectional"))
      (node (ref "Q3") (pin "D") (pinfunction "D_D") (pintype "bidirectional"))
      (node (ref "Q5") (pin "D") (pinfunction "D_D") (pintype "bidirectional"))
      (node (ref "R15") (pin "1") (pinfunction "1_1") (pintype "passive"))
      (node (ref "U1") (pin "29") (pinfunction "PVDD1_29") (pintype "bidirectional"))
      (node (ref "U1") (pin "53") (pinfunction "PVDD2_1_53") (pintype "bidirectional"))
      (node (ref "U1") (pin "54") (pinfunction "PVDD2_2_54") (pintype "bidirectional"))
    )
    (net (code "66") (name "unconnected-(U1-EN_BUCK-Pad55)") (class "Default")
      (node (ref "U1") (pin "55") (pinfunction "EN_BUCK_55") (pintype "bidirectional"))
    )
    (net (code "67") (name "unconnected-(U1-PWRGD-Pad4)") (class "Default")
      (node (ref "U1") (pin "4") (pinfunction "PWRGD_4") (pintype "bidirectional"))
    )
    (net (code "68") (name "unconnected-(U1-SN2-Pad31)") (class "Default")
      (node (ref "U1") (pin "31") (pinfunction "SN2_31") (pintype "bidirectional"))
    )
    (net (code "69") (name "unconnected-(U1-SO2-Pad26)") (class "Default")
      (node (ref "U1") (pin "26") (pinfunction "SO2_26") (pintype "bidirectional"))
    )
    (net (code "70") (name "unconnected-(U1-SP2-Pad30)") (class "Default")
      (node (ref "U1") (pin "30") (pinfunction "SP2_30") (pintype "bidirectional"))
    )
    (net (code "71") (name "unconnected-(U1-~{OCTW}-Pad5)") (class "Default")
      (node (ref "U1") (pin "5") (pinfunction "~{OCTW}_5") (pintype "bidirectional"))
    )
    (net (code "72") (name "unconnected-(U2-1{slash}TX1{slash}T-Pad1)") (class "Default")
      (node (ref "U2") (pin "1") (pinfunction "1/TX1/T_1") (pintype "bidirectional"))
    )
    (net (code "73") (name "unconnected-(U2-23{slash}A9{slash}T{slash}PWM-Pad23{slash}A9)") (class "Default")
      (node (ref "U2") (pin "23/A9") (pinfunction "23/A9/T/PWM_23/A9") (pintype "bidirectional"))
    )
  )
)
